# NAND_PullUp_OD.net
KiCad netlist of a schematic drawn in Altium Designer
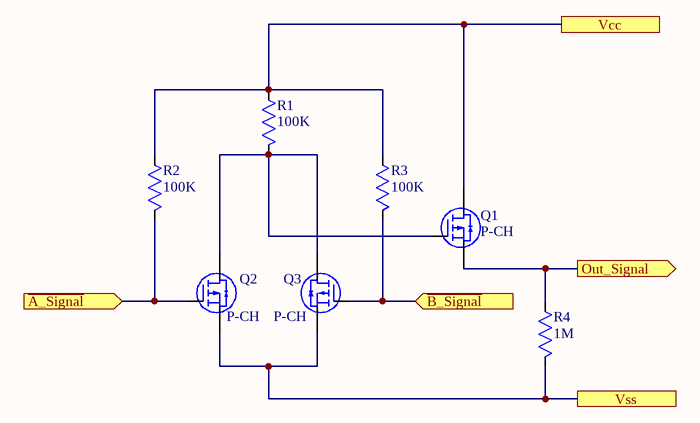
[diagram p0: NAND_PullUp_OD.SchDoc]

(export (version "E")
  (design (tool "Eeschema 10.0.6"))
  (components
    (comp (ref "Q1")
      (value "SI2301DS-T1")
      (footprint "SOT-23")
      (description "Trans MOSFET P-CH 20V 2.3A 3-Pin TO-236 T/R")
      (fields (field (name "MANUFACTURER") "Vishay Siliconix") (field (name "POLARITY") "P-CH"))
      (libsource (lib "ZGR") (part "SI2301DS-T1"))
    )
    (comp (ref "Q2")
      (value "SI2301DS-T1")
      (footprint "SOT-23")
      (description "Trans MOSFET P-CH 20V 2.3A 3-Pin TO-236 T/R")
      (fields (field (name "MANUFACTURER") "Vishay Siliconix") (field (name "POLARITY") "P-CH"))
      (libsource (lib "ZGR") (part "SI2301DS-T1"))
    )
    (comp (ref "Q3")
      (value "SI2301DS-T1")
      (footprint "SOT-23")
      (description "Trans MOSFET P-CH 20V 2.3A 3-Pin TO-236 T/R")
      (fields (field (name "MANUFACTURER") "Vishay Siliconix") (field (name "POLARITY") "P-CH"))
      (libsource (lib "ZGR") (part "SI2301DS-T1"))
    )
    (comp (ref "R1")
      (value "100K")
      (footprint "RES_0402")
      (fields (field (name "Comment") "Res"))
      (libsource (lib "ZGR") (part "Res"))
    )
    (comp (ref "R2")
      (value "100K")
      (footprint "RES_0402")
      (fields (field (name "Comment") "Res"))
      (libsource (lib "ZGR") (part "Res"))
    )
    (comp (ref "R3")
      (value "100K")
      (footprint "RES_0402")
      (fields (field (name "Comment") "Res"))
      (libsource (lib "ZGR") (part "Res"))
    )
    (comp (ref "R4")
      (value "1M")
      (footprint "RES_0402")
      (fields (field (name "Comment") "Res"))
      (libsource (lib "ZGR") (part "Res"))
    )
  )
  (nets
    (net (code "1") (name "/A_Signal") (class "Default")
      (node (ref "Q2") (pin "2") (pinfunction "2_2") (pintype "passive"))
      (node (ref "R2") (pin "1") (pinfunction "1_1") (pintype "passive"))
    )
    (net (code "2") (name "/B_Signal") (class "Default")
      (node (ref "Q3") (pin "2") (pinfunction "2_2") (pintype "passive"))
      (node (ref "R3") (pin "1") (pinfunction "1_1") (pintype "passive"))
    )
    (net (code "3") (name "/Out_Signal") (class "Default")
      (node (ref "Q1") (pin "3") (pinfunction "3_3") (pintype "passive"))
      (node (ref "R4") (pin "2") (pinfunction "2_2") (pintype "passive"))
    )
    (net (code "4") (name "/Vcc") (class "Default")
      (node (ref "Q1") (pin "1") (pinfunction "1_1") (pintype "passive"))
      (node (ref "R1") (pin "2") (pinfunction "2_2") (pintype "passive"))
      (node (ref "R2") (pin "2") (pinfunction "2_2") (pintype "passive"))
      (node (ref "R3") (pin "2") (pinfunction "2_2") (pintype "passive"))
    )
    (net (code "5") (name "/Vss") (class "Default")
      (node (ref "Q2") (pin "3") (pinfunction "3_3") (pintype "passive"))
      (node (ref "Q3") (pin "3") (pinfunction "3_3") (pintype "passive"))
      (node (ref "R4") (pin "1") (pinfunction "1_1") (pintype "passive"))
    )
    (net (code "6") (name "Net-(Q1-Pad2)") (class "Default")
      (node (ref "Q1") (pin "2") (pinfunction "2_2") (pintype "passive"))
      (node (ref "Q2") (pin "1") (pinfunction "1_1") (pintype "passive"))
      (node (ref "Q3") (pin "1") (pinfunction "1_1") (pintype "passive"))
      (node (ref "R1") (pin "1") (pinfunction "1_1") (pintype "passive"))
    )
  )
)
